# SparkFun_RedStick-ProtoPanel-v01.net
KiCad netlist of a schematic drawn in EAGLE
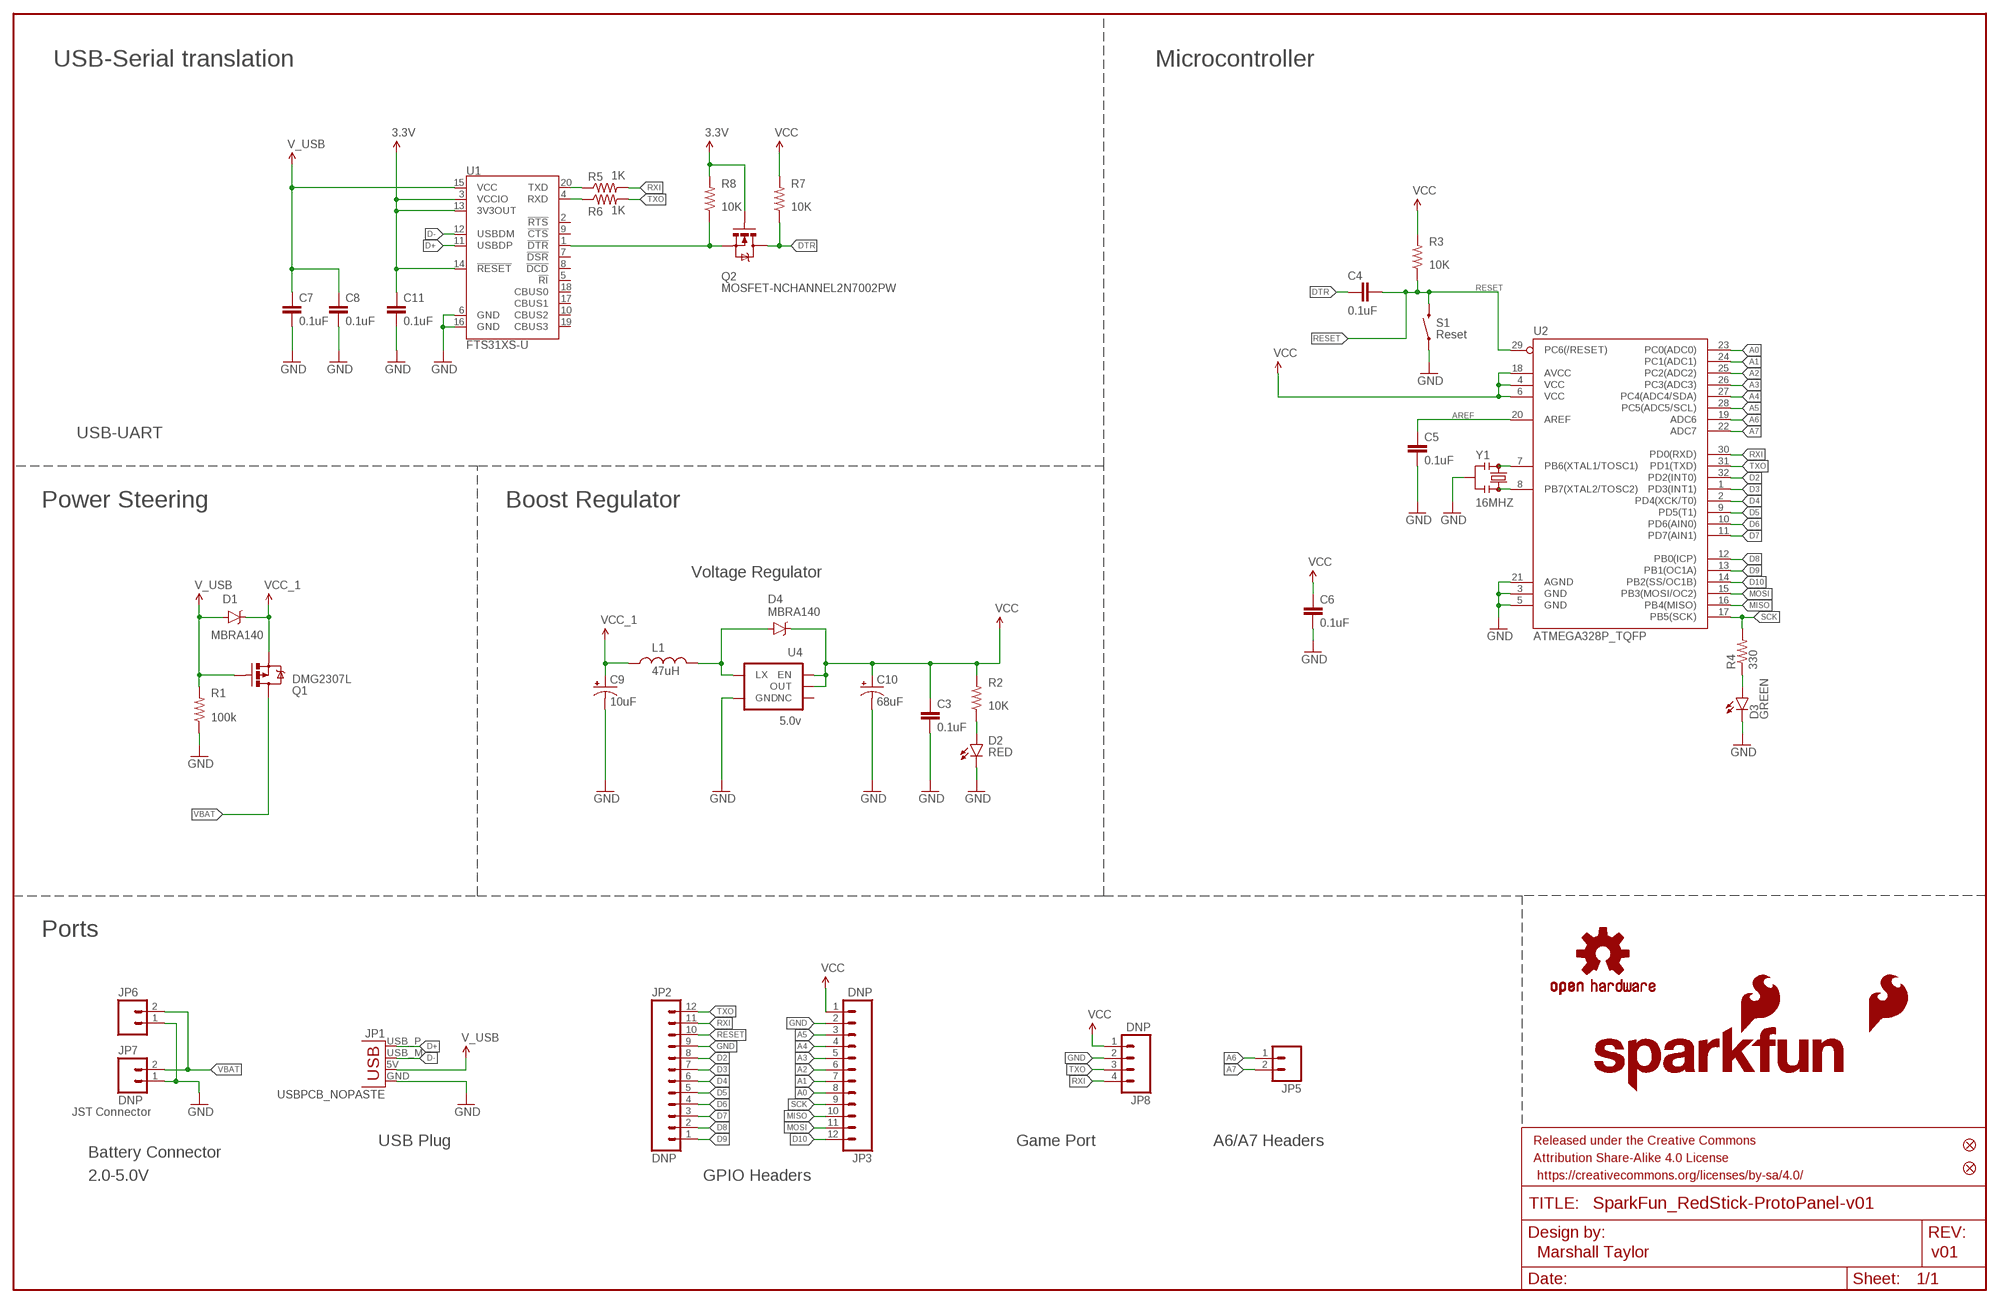
[diagram p0: schematic, sheet 1]

(export (version "E")
  (design (tool "Eeschema 10.0.6"))
  (components
    (comp (ref "C3")
      (value "0.1uF")
      (footprint "eagle-import:0603-CAP")
      (libsource (lib "eagle-import") (part "0.1UF-25V(+80/-20%)(0603)"))
    )
    (comp (ref "C4")
      (value "0.1uF")
      (footprint "eagle-import:0603-CAP")
      (libsource (lib "eagle-import") (part "0.1UF-25V(+80/-20%)(0603)"))
    )
    (comp (ref "C5")
      (value "0.1uF")
      (footprint "eagle-import:0603-CAP")
      (libsource (lib "eagle-import") (part "0.1UF-25V(+80/-20%)(0603)"))
    )
    (comp (ref "C6")
      (value "0.1uF")
      (footprint "eagle-import:0603-CAP")
      (libsource (lib "eagle-import") (part "0.1UF-25V(+80/-20%)(0603)"))
    )
    (comp (ref "C7")
      (value "0.1uF")
      (footprint "eagle-import:0603-CAP")
      (libsource (lib "eagle-import") (part "0.1UF-25V(+80/-20%)(0603)"))
    )
    (comp (ref "C8")
      (value "0.1uF")
      (footprint "eagle-import:0603-CAP")
      (libsource (lib "eagle-import") (part "0.1UF-25V(+80/-20%)(0603)"))
    )
    (comp (ref "C9")
      (value "10uF")
      (footprint "eagle-import:EIA3216")
      (libsource (lib "eagle-import") (part "10UF-16V-10%(TANT)"))
    )
    (comp (ref "C10")
      (value "68uF")
      (footprint "eagle-import:EIA3528")
      (libsource (lib "eagle-import") (part "68UF-10V-10%(TANT)"))
    )
    (comp (ref "C11")
      (value "0.1uF")
      (footprint "eagle-import:0603-CAP")
      (libsource (lib "eagle-import") (part "0.1UF-25V(+80/-20%)(0603)"))
    )
    (comp (ref "D1")
      (value "MBRA140")
      (footprint "eagle-import:SMA-DIODE")
      (libsource (lib "eagle-import") (part "DIODE-SCHOTTKY-MBRA140"))
    )
    (comp (ref "D2")
      (value "RED")
      (footprint "eagle-import:LED-0603")
      (libsource (lib "eagle-import") (part "LED-RED0603"))
    )
    (comp (ref "D3")
      (value "GREEN")
      (footprint "eagle-import:LED-0603")
      (libsource (lib "eagle-import") (part "LED-GREEN0603"))
    )
    (comp (ref "D4")
      (value "MBRA140")
      (footprint "eagle-import:SMA-DIODE")
      (libsource (lib "eagle-import") (part "DIODE-SCHOTTKY-MBRA140"))
    )
    (comp (ref "FID1")
      (value "FIDUCIAL1X2")
      (footprint "eagle-import:FIDUCIAL-1X2")
      (libsource (lib "eagle-import") (part "FIDUCIAL1X2"))
    )
    (comp (ref "FID2")
      (value "FIDUCIAL1X2")
      (footprint "eagle-import:FIDUCIAL-1X2")
      (libsource (lib "eagle-import") (part "FIDUCIAL1X2"))
    )
    (comp (ref "FRAME2")
      (value "FRAME-LEDGER")
      (footprint "eagle-import:CREATIVE_COMMONS")
      (libsource (lib "eagle-import") (part "FRAME-LEDGER"))
    )
    (comp (ref "JP1")
      (value "USBPCB_NOPASTE")
      (footprint "eagle-import:USB-A-PCB-NOPASTE")
      (libsource (lib "eagle-import") (part "USBPCB_NOPASTE"))
    )
    (comp (ref "JP2")
      (value "DNP")
      (footprint "eagle-import:1X12_LOCK_NO_SILK")
      (libsource (lib "eagle-import") (part "M12LOCK_NO_SILK"))
    )
    (comp (ref "JP3")
      (value "DNP")
      (footprint "eagle-import:1X12_LOCK_NO_SILK")
      (libsource (lib "eagle-import") (part "M12LOCK_NO_SILK"))
    )
    (comp (ref "JP5")
      (value "M021X02_NO_SILK")
      (footprint "eagle-import:1X02_NO_SILK")
      (libsource (lib "eagle-import") (part "M021X02_NO_SILK"))
    )
    (comp (ref "JP6")
      (value "M021X02_NO_SILK")
      (footprint "eagle-import:1X02_NO_SILK")
      (libsource (lib "eagle-import") (part "M021X02_NO_SILK"))
    )
    (comp (ref "JP7")
      (value "DNP")
      (footprint "eagle-import:JST-2-PTH")
      (libsource (lib "eagle-import") (part "M02JST-PTH-2"))
    )
    (comp (ref "JP8")
      (value "DNP")
      (footprint "eagle-import:1X04")
      (libsource (lib "eagle-import") (part "M04PTH"))
    )
    (comp (ref "L1")
      (value "47uH")
      (footprint "eagle-import:CR54")
      (libsource (lib "eagle-import") (part "INDUCTORCR54-47UH"))
    )
    (comp (ref "LOGO1")
      (value "SFE_LOGO_FLAME.1_INCH")
      (footprint "eagle-import:SFE_LOGO_FLAME_.1")
      (libsource (lib "eagle-import") (part "SFE_LOGO_FLAME.1_INCH"))
    )
    (comp (ref "LOGO2")
      (value "OSHW-LOGOS")
      (footprint "eagle-import:OSHW-LOGO-S")
      (libsource (lib "eagle-import") (part "OSHW-LOGOS"))
    )
    (comp (ref "Q1")
      (value "DMG2307L")
      (footprint "eagle-import:SOT23-3")
      (libsource (lib "eagle-import") (part "MOSFET-PCHANNELDMG2307L"))
    )
    (comp (ref "Q2")
      (value "MOSFET-NCHANNEL2N7002PW")
      (footprint "eagle-import:SOT323")
      (libsource (lib "eagle-import") (part "MOSFET-NCHANNEL2N7002PW"))
    )
    (comp (ref "R1")
      (value "100k")
      (footprint "eagle-import:0603-RES")
      (libsource (lib "eagle-import") (part "100KOHM-1/10W-1%(0603)"))
    )
    (comp (ref "R2")
      (value "10K")
      (footprint "eagle-import:0603-RES")
      (libsource (lib "eagle-import") (part "10KOHM-1/10W-1%(0603)0603"))
    )
    (comp (ref "R3")
      (value "10K")
      (footprint "eagle-import:0603-RES")
      (libsource (lib "eagle-import") (part "10KOHM-1/10W-1%(0603)0603"))
    )
    (comp (ref "R4")
      (value "330")
      (footprint "eagle-import:0603-RES")
      (libsource (lib "eagle-import") (part "330OHM1/10W1%(0603)"))
    )
    (comp (ref "R5")
      (value "1K")
      (footprint "eagle-import:0603-RES")
      (libsource (lib "eagle-import") (part "1KOHM-1/10W-1%(0603)"))
    )
    (comp (ref "R6")
      (value "1K")
      (footprint "eagle-import:0603-RES")
      (libsource (lib "eagle-import") (part "1KOHM-1/10W-1%(0603)"))
    )
    (comp (ref "R7")
      (value "10K")
      (footprint "eagle-import:0603-RES")
      (libsource (lib "eagle-import") (part "10KOHM-1/10W-1%(0603)0603"))
    )
    (comp (ref "R8")
      (value "10K")
      (footprint "eagle-import:0603-RES")
      (libsource (lib "eagle-import") (part "10KOHM-1/10W-1%(0603)0603"))
    )
    (comp (ref "S1")
      (value "SWITCH-MOMENTARY-2SMD-REDUNDANT")
      (footprint "eagle-import:TACTILE-SWITCH-SMD")
      (fields (field (name "FUNC") "Reset"))
      (libsource (lib "eagle-import") (part "SWITCH-MOMENTARY-2SMD-REDUNDANT"))
    )
    (comp (ref "U$1")
      (value "SFE_LOGO_NAME_FLAME.1_INCH")
      (footprint "eagle-import:SFE_LOGO_NAME_FLAME_.1")
      (libsource (lib "eagle-import") (part "SFE_LOGO_NAME_FLAME.1_INCH"))
    )
    (comp (ref "U1")
      (value "FTS31XS-U")
      (footprint "eagle-import:SSOP20_L")
      (libsource (lib "eagle-import") (part "FT231XS"))
    )
    (comp (ref "U2")
      (value "ATMEGA328P_TQFP")
      (footprint "eagle-import:TQFP32-08")
      (libsource (lib "eagle-import") (part "ATMEGA328P_TQFP"))
    )
    (comp (ref "U4")
      (value "5.0v")
      (footprint "eagle-import:SOT23-5")
      (libsource (lib "eagle-import") (part "V_REG_NCP1400_5V"))
    )
    (comp (ref "Y1")
      (value "16MHZ")
      (footprint "eagle-import:RESONATOR-SMD")
      (libsource (lib "eagle-import") (part "RESONATOR16MHZ"))
    )
  )
  (nets
    (net (code "1") (name "/AREF") (class "Default")
      (node (ref "C5") (pin "1") (pinfunction "1_1") (pintype "passive"))
      (node (ref "U2") (pin "20") (pinfunction "AREF_20") (pintype "bidirectional"))
    )
    (net (code "2") (name "3.3V") (class "Default")
      (node (ref "C11") (pin "1") (pinfunction "1_1") (pintype "passive"))
      (node (ref "Q2") (pin "1") (pinfunction "G_1") (pintype "passive"))
      (node (ref "R8") (pin "2") (pinfunction "2_2") (pintype "passive"))
      (node (ref "U1") (pin "13") (pinfunction "3V3OUT_13") (pintype "bidirectional"))
      (node (ref "U1") (pin "14") (pinfunction "~{RESET}_14") (pintype "bidirectional"))
      (node (ref "U1") (pin "3") (pinfunction "VCCIO_3") (pintype "bidirectional"))
    )
    (net (code "3") (name "A0") (class "Default")
      (node (ref "JP3") (pin "8") (pinfunction "8_8") (pintype "passive"))
      (node (ref "U2") (pin "23") (pinfunction "PC0(ADC0)_23") (pintype "bidirectional"))
    )
    (net (code "4") (name "A1") (class "Default")
      (node (ref "JP3") (pin "7") (pinfunction "7_7") (pintype "passive"))
      (node (ref "U2") (pin "24") (pinfunction "PC1(ADC1)_24") (pintype "bidirectional"))
    )
    (net (code "5") (name "A2") (class "Default")
      (node (ref "JP3") (pin "6") (pinfunction "6_6") (pintype "passive"))
      (node (ref "U2") (pin "25") (pinfunction "PC2(ADC2)_25") (pintype "bidirectional"))
    )
    (net (code "6") (name "A3") (class "Default")
      (node (ref "JP3") (pin "5") (pinfunction "5_5") (pintype "passive"))
      (node (ref "U2") (pin "26") (pinfunction "PC3(ADC3)_26") (pintype "bidirectional"))
    )
    (net (code "7") (name "A4") (class "Default")
      (node (ref "JP3") (pin "4") (pinfunction "4_4") (pintype "passive"))
      (node (ref "U2") (pin "27") (pinfunction "PC4(ADC4/SDA)_27") (pintype "bidirectional"))
    )
    (net (code "8") (name "A5") (class "Default")
      (node (ref "JP3") (pin "3") (pinfunction "3_3") (pintype "passive"))
      (node (ref "U2") (pin "28") (pinfunction "PC5(ADC5/SCL)_28") (pintype "bidirectional"))
    )
    (net (code "9") (name "A6") (class "Default")
      (node (ref "JP5") (pin "1") (pinfunction "1_1") (pintype "passive"))
      (node (ref "U2") (pin "19") (pinfunction "ADC6_19") (pintype "bidirectional"))
    )
    (net (code "10") (name "A7") (class "Default")
      (node (ref "JP5") (pin "2") (pinfunction "2_2") (pintype "passive"))
      (node (ref "U2") (pin "22") (pinfunction "ADC7_22") (pintype "bidirectional"))
    )
    (net (code "11") (name "D+") (class "Default")
      (node (ref "JP1") (pin "USB_P") (pinfunction "D+_USB_P") (pintype "bidirectional"))
      (node (ref "U1") (pin "11") (pinfunction "USBDP_11") (pintype "bidirectional"))
    )
    (net (code "12") (name "D-") (class "Default")
      (node (ref "JP1") (pin "USB_M") (pinfunction "D-_USB_M") (pintype "bidirectional"))
      (node (ref "U1") (pin "12") (pinfunction "USBDM_12") (pintype "bidirectional"))
    )
    (net (code "13") (name "D2") (class "Default")
      (node (ref "JP2") (pin "8") (pinfunction "8_8") (pintype "passive"))
      (node (ref "U2") (pin "32") (pinfunction "PD2(INT0)_32") (pintype "bidirectional"))
    )
    (net (code "14") (name "D3") (class "Default")
      (node (ref "JP2") (pin "7") (pinfunction "7_7") (pintype "passive"))
      (node (ref "U2") (pin "1") (pinfunction "PD3(INT1)_1") (pintype "bidirectional"))
    )
    (net (code "15") (name "D4") (class "Default")
      (node (ref "JP2") (pin "6") (pinfunction "6_6") (pintype "passive"))
      (node (ref "U2") (pin "2") (pinfunction "PD4(XCK/T0)_2") (pintype "bidirectional"))
    )
    (net (code "16") (name "D5") (class "Default")
      (node (ref "JP2") (pin "5") (pinfunction "5_5") (pintype "passive"))
      (node (ref "U2") (pin "9") (pinfunction "PD5(T1)_9") (pintype "bidirectional"))
    )
    (net (code "17") (name "D6") (class "Default")
      (node (ref "JP2") (pin "4") (pinfunction "4_4") (pintype "passive"))
      (node (ref "U2") (pin "10") (pinfunction "PD6(AIN0)_10") (pintype "bidirectional"))
    )
    (net (code "18") (name "D7") (class "Default")
      (node (ref "JP2") (pin "3") (pinfunction "3_3") (pintype "passive"))
      (node (ref "U2") (pin "11") (pinfunction "PD7(AIN1)_11") (pintype "bidirectional"))
    )
    (net (code "19") (name "D8") (class "Default")
      (node (ref "JP2") (pin "2") (pinfunction "2_2") (pintype "passive"))
      (node (ref "U2") (pin "12") (pinfunction "PB0(ICP)_12") (pintype "bidirectional"))
    )
    (net (code "20") (name "D9") (class "Default")
      (node (ref "JP2") (pin "1") (pinfunction "1_1") (pintype "passive"))
      (node (ref "U2") (pin "13") (pinfunction "PB1(OC1A)_13") (pintype "bidirectional"))
    )
    (net (code "21") (name "D10") (class "Default")
      (node (ref "JP3") (pin "12") (pinfunction "12_12") (pintype "passive"))
      (node (ref "U2") (pin "14") (pinfunction "PB2(SS/OC1B)_14") (pintype "bidirectional"))
    )
    (net (code "22") (name "DTR") (class "Default")
      (node (ref "C4") (pin "1") (pinfunction "1_1") (pintype "passive"))
      (node (ref "Q2") (pin "3") (pinfunction "D_3") (pintype "passive"))
      (node (ref "R7") (pin "1") (pinfunction "1_1") (pintype "passive"))
    )
    (net (code "23") (name "GND") (class "Default")
      (node (ref "C10") (pin "C") (pinfunction "-_C") (pintype "passive"))
      (node (ref "C11") (pin "2") (pinfunction "2_2") (pintype "passive"))
      (node (ref "C3") (pin "2") (pinfunction "2_2") (pintype "passive"))
      (node (ref "C5") (pin "2") (pinfunction "2_2") (pintype "passive"))
      (node (ref "C6") (pin "2") (pinfunction "2_2") (pintype "passive"))
      (node (ref "C7") (pin "2") (pinfunction "2_2") (pintype "passive"))
      (node (ref "C8") (pin "2") (pinfunction "2_2") (pintype "passive"))
      (node (ref "C9") (pin "C") (pinfunction "-_C") (pintype "passive"))
      (node (ref "D2") (pin "C") (pinfunction "C_C") (pintype "passive"))
      (node (ref "D3") (pin "C") (pinfunction "C_C") (pintype "passive"))
      (node (ref "JP1") (pin "GND") (pinfunction "GND_GND") (pintype "bidirectional"))
      (node (ref "JP2") (pin "9") (pinfunction "9_9") (pintype "passive"))
      (node (ref "JP3") (pin "2") (pinfunction "2_2") (pintype "passive"))
      (node (ref "JP6") (pin "1") (pinfunction "1_1") (pintype "passive"))
      (node (ref "JP7") (pin "1") (pinfunction "1_1") (pintype "passive"))
      (node (ref "JP8") (pin "2") (pinfunction "2_2") (pintype "passive"))
      (node (ref "R1") (pin "1") (pinfunction "1_1") (pintype "passive"))
      (node (ref "S1") (pin "1") (pinfunction "1_1") (pintype "passive"))
      (node (ref "S1") (pin "2") (pinfunction "1_2") (pintype "passive"))
      (node (ref "U1") (pin "16") (pinfunction "GND_16") (pintype "bidirectional"))
      (node (ref "U1") (pin "6") (pinfunction "GND_6") (pintype "bidirectional"))
      (node (ref "U2") (pin "21") (pinfunction "AGND_21") (pintype "bidirectional"))
      (node (ref "U2") (pin "3") (pinfunction "GND_3") (pintype "bidirectional"))
      (node (ref "U2") (pin "5") (pinfunction "GND_5") (pintype "bidirectional"))
      (node (ref "U4") (pin "4") (pinfunction "GND_4") (pintype "input"))
      (node (ref "Y1") (pin "2") (pinfunction "2_2") (pintype "passive"))
    )
    (net (code "24") (name "MISO") (class "Default")
      (node (ref "JP3") (pin "10") (pinfunction "10_10") (pintype "passive"))
      (node (ref "U2") (pin "16") (pinfunction "PB4(MISO)_16") (pintype "bidirectional"))
    )
    (net (code "25") (name "MOSI") (class "Default")
      (node (ref "JP3") (pin "11") (pinfunction "11_11") (pintype "passive"))
      (node (ref "U2") (pin "15") (pinfunction "PB3(MOSI/OC2)_15") (pintype "bidirectional"))
    )
    (net (code "26") (name "Net-(D2-PadA)") (class "Default")
      (node (ref "D2") (pin "A") (pinfunction "A_A") (pintype "passive"))
      (node (ref "R2") (pin "1") (pinfunction "1_1") (pintype "passive"))
    )
    (net (code "27") (name "Net-(D3-PadA)") (class "Default")
      (node (ref "D3") (pin "A") (pinfunction "A_A") (pintype "passive"))
      (node (ref "R4") (pin "1") (pinfunction "1_1") (pintype "passive"))
    )
    (net (code "28") (name "Net-(L1-2)") (class "Default")
      (node (ref "D4") (pin "A") (pinfunction "A_A") (pintype "passive"))
      (node (ref "L1") (pin "P$2") (pinfunction "2_P$2") (pintype "passive"))
      (node (ref "U4") (pin "5") (pinfunction "LX_5") (pintype "input"))
    )
    (net (code "29") (name "Net-(Q2-S)") (class "Default")
      (node (ref "Q2") (pin "2") (pinfunction "S_2") (pintype "passive"))
      (node (ref "R8") (pin "1") (pinfunction "1_1") (pintype "passive"))
      (node (ref "U1") (pin "1") (pinfunction "~{DTR}_1") (pintype "bidirectional"))
    )
    (net (code "30") (name "Net-(U1-RXD)") (class "Default")
      (node (ref "R6") (pin "1") (pinfunction "1_1") (pintype "passive"))
      (node (ref "U1") (pin "4") (pinfunction "RXD_4") (pintype "bidirectional"))
    )
    (net (code "31") (name "Net-(U1-TXD)") (class "Default")
      (node (ref "R5") (pin "1") (pinfunction "1_1") (pintype "passive"))
      (node (ref "U1") (pin "20") (pinfunction "TXD_20") (pintype "bidirectional"))
    )
    (net (code "32") (name "Net-(U2-PB6(XTAL1{slash}TOSC1))") (class "Default")
      (node (ref "U2") (pin "7") (pinfunction "PB6(XTAL1/TOSC1)_7") (pintype "bidirectional"))
      (node (ref "Y1") (pin "1") (pinfunction "1_1") (pintype "passive"))
    )
    (net (code "33") (name "Net-(U2-PB7(XTAL2{slash}TOSC2))") (class "Default")
      (node (ref "U2") (pin "8") (pinfunction "PB7(XTAL2/TOSC2)_8") (pintype "bidirectional"))
      (node (ref "Y1") (pin "3") (pinfunction "3_3") (pintype "passive"))
    )
    (net (code "34") (name "RESET") (class "Default")
      (node (ref "C4") (pin "2") (pinfunction "2_2") (pintype "passive"))
      (node (ref "JP2") (pin "10") (pinfunction "10_10") (pintype "passive"))
      (node (ref "R3") (pin "1") (pinfunction "1_1") (pintype "passive"))
      (node (ref "S1") (pin "3") (pinfunction "2_3") (pintype "passive"))
      (node (ref "S1") (pin "4") (pinfunction "2_4") (pintype "passive"))
      (node (ref "U2") (pin "29") (pinfunction "PC6(/RESET)_29") (pintype "bidirectional"))
    )
    (net (code "35") (name "RXI") (class "Default")
      (node (ref "JP2") (pin "11") (pinfunction "11_11") (pintype "passive"))
      (node (ref "JP8") (pin "4") (pinfunction "4_4") (pintype "passive"))
      (node (ref "R5") (pin "2") (pinfunction "2_2") (pintype "passive"))
      (node (ref "U2") (pin "30") (pinfunction "PD0(RXD)_30") (pintype "bidirectional"))
    )
    (net (code "36") (name "SCK") (class "Default")
      (node (ref "JP3") (pin "9") (pinfunction "9_9") (pintype "passive"))
      (node (ref "R4") (pin "2") (pinfunction "2_2") (pintype "passive"))
      (node (ref "U2") (pin "17") (pinfunction "PB5(SCK)_17") (pintype "bidirectional"))
    )
    (net (code "37") (name "TXO") (class "Default")
      (node (ref "JP2") (pin "12") (pinfunction "12_12") (pintype "passive"))
      (node (ref "JP8") (pin "3") (pinfunction "3_3") (pintype "passive"))
      (node (ref "R6") (pin "2") (pinfunction "2_2") (pintype "passive"))
      (node (ref "U2") (pin "31") (pinfunction "PD1(TXD)_31") (pintype "bidirectional"))
    )
    (net (code "38") (name "VBAT") (class "Default")
      (node (ref "JP6") (pin "2") (pinfunction "2_2") (pintype "passive"))
      (node (ref "JP7") (pin "2") (pinfunction "2_2") (pintype "passive"))
      (node (ref "Q1") (pin "3") (pinfunction "D_3") (pintype "passive"))
    )
    (net (code "39") (name "VCC") (class "Default")
      (node (ref "C10") (pin "A") (pinfunction "+_A") (pintype "passive"))
      (node (ref "C3") (pin "1") (pinfunction "1_1") (pintype "passive"))
      (node (ref "C6") (pin "1") (pinfunction "1_1") (pintype "passive"))
      (node (ref "D4") (pin "C") (pinfunction "C_C") (pintype "passive"))
      (node (ref "JP3") (pin "1") (pinfunction "1_1") (pintype "passive"))
      (node (ref "JP8") (pin "1") (pinfunction "1_1") (pintype "passive"))
      (node (ref "R2") (pin "2") (pinfunction "2_2") (pintype "passive"))
      (node (ref "R3") (pin "2") (pinfunction "2_2") (pintype "passive"))
      (node (ref "R7") (pin "2") (pinfunction "2_2") (pintype "passive"))
      (node (ref "U2") (pin "18") (pinfunction "AVCC_18") (pintype "bidirectional"))
      (node (ref "U2") (pin "4") (pinfunction "VCC_4") (pintype "bidirectional"))
      (node (ref "U2") (pin "6") (pinfunction "VCC_6") (pintype "bidirectional"))
      (node (ref "U4") (pin "1") (pinfunction "EN_1") (pintype "input"))
      (node (ref "U4") (pin "2") (pinfunction "OUT_2") (pintype "passive"))
    )
    (net (code "40") (name "VCC_1") (class "Default")
      (node (ref "C9") (pin "A") (pinfunction "+_A") (pintype "passive"))
      (node (ref "D1") (pin "C") (pinfunction "C_C") (pintype "passive"))
      (node (ref "L1") (pin "P$1") (pinfunction "1_P$1") (pintype "passive"))
      (node (ref "Q1") (pin "2") (pinfunction "S_2") (pintype "passive"))
    )
    (net (code "41") (name "V_USB") (class "Default")
      (node (ref "C7") (pin "1") (pinfunction "1_1") (pintype "passive"))
      (node (ref "C8") (pin "1") (pinfunction "1_1") (pintype "passive"))
      (node (ref "D1") (pin "A") (pinfunction "A_A") (pintype "passive"))
      (node (ref "JP1") (pin "5V") (pinfunction "VBUS_5V") (pintype "bidirectional"))
      (node (ref "Q1") (pin "1") (pinfunction "G_1") (pintype "passive"))
      (node (ref "R1") (pin "2") (pinfunction "2_2") (pintype "passive"))
      (node (ref "U1") (pin "15") (pinfunction "VCC_15") (pintype "bidirectional"))
    )
    (net (code "42") (name "unconnected-(U1-CBUS0-Pad18)") (class "Default")
      (node (ref "U1") (pin "18") (pinfunction "CBUS0_18") (pintype "bidirectional"))
    )
    (net (code "43") (name "unconnected-(U1-CBUS1-Pad17)") (class "Default")
      (node (ref "U1") (pin "17") (pinfunction "CBUS1_17") (pintype "bidirectional"))
    )
    (net (code "44") (name "unconnected-(U1-CBUS2-Pad10)") (class "Default")
      (node (ref "U1") (pin "10") (pinfunction "CBUS2_10") (pintype "bidirectional"))
    )
    (net (code "45") (name "unconnected-(U1-CBUS3-Pad19)") (class "Default")
      (node (ref "U1") (pin "19") (pinfunction "CBUS3_19") (pintype "bidirectional"))
    )
    (net (code "46") (name "unconnected-(U1-~{CTS}-Pad9)") (class "Default")
      (node (ref "U1") (pin "9") (pinfunction "~{CTS}_9") (pintype "bidirectional"))
    )
    (net (code "47") (name "unconnected-(U1-~{DCD}-Pad8)") (class "Default")
      (node (ref "U1") (pin "8") (pinfunction "~{DCD}_8") (pintype "bidirectional"))
    )
    (net (code "48") (name "unconnected-(U1-~{DSR}-Pad7)") (class "Default")
      (node (ref "U1") (pin "7") (pinfunction "~{DSR}_7") (pintype "bidirectional"))
    )
    (net (code "49") (name "unconnected-(U1-~{RI}-Pad5)") (class "Default")
      (node (ref "U1") (pin "5") (pinfunction "~{RI}_5") (pintype "bidirectional"))
    )
    (net (code "50") (name "unconnected-(U1-~{RTS}-Pad2)") (class "Default")
      (node (ref "U1") (pin "2") (pinfunction "~{RTS}_2") (pintype "bidirectional"))
    )
    (net (code "51") (name "unconnected-(U4-NC-Pad3)") (class "Default")
      (node (ref "U4") (pin "3") (pinfunction "NC_3") (pintype "input"))
    )
  )
)
